# OECU_BASE3.net
KiCad netlist of a schematic drawn in Altium Designer
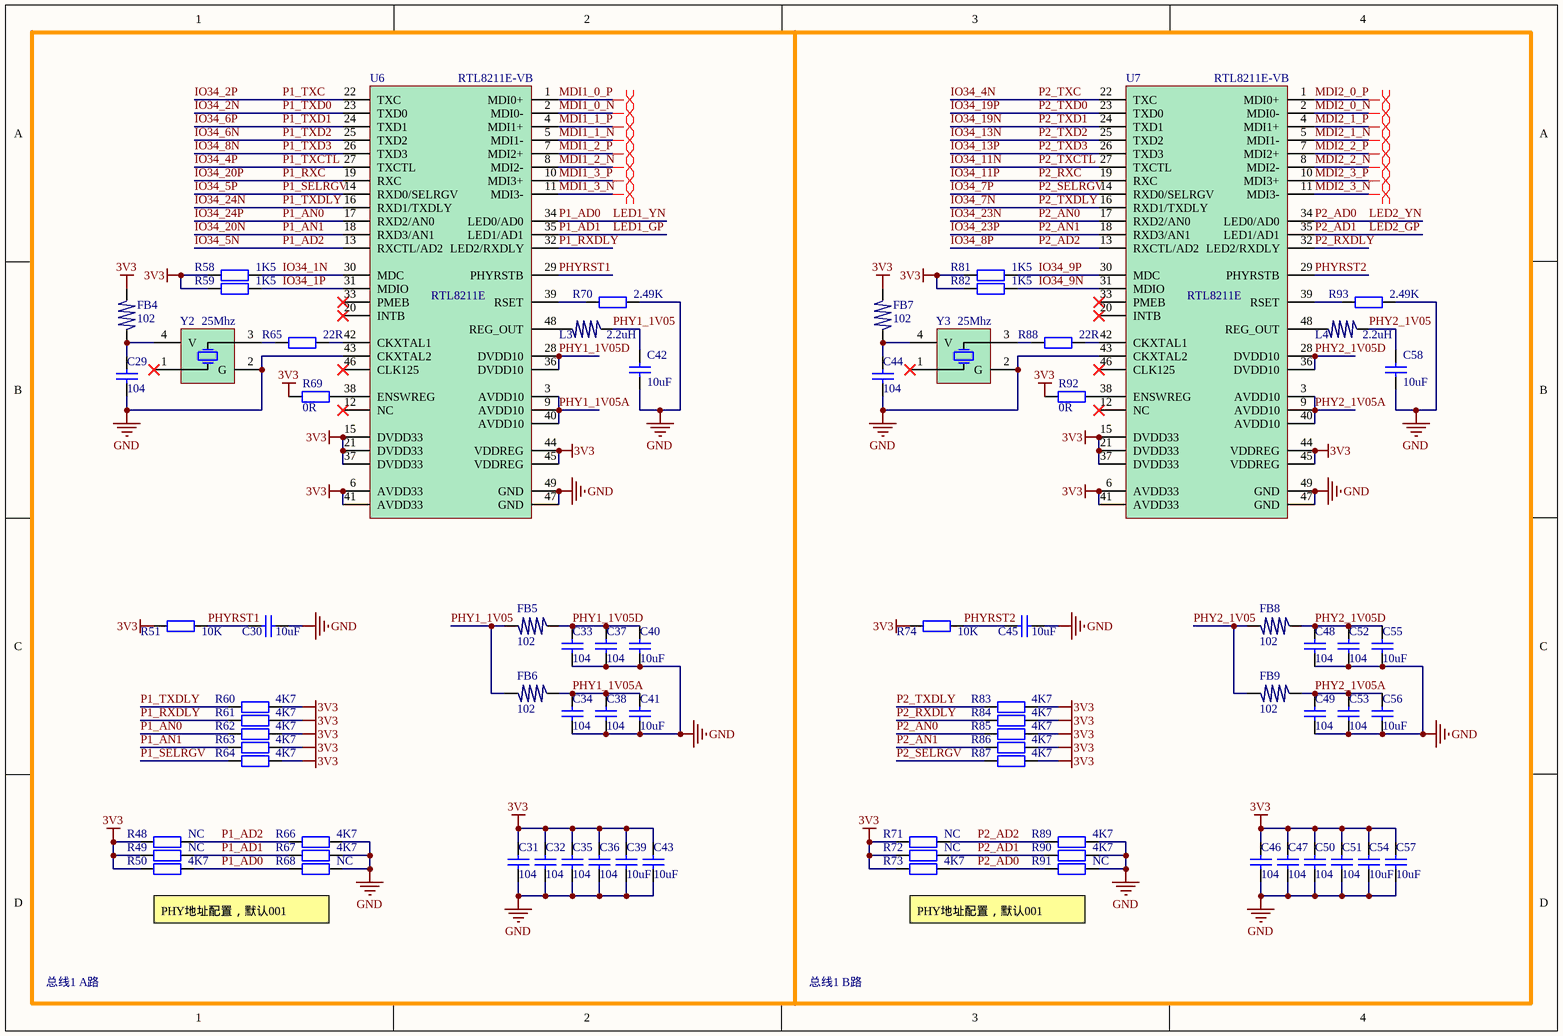
[diagram p0: OECU_BASE3.SchDoc]

(export (version "E")
  (design (tool "Eeschema 10.0.6"))
  (components
    (comp (ref "C29")
      (value "104")
      (footprint "0402")
      (description "贴片电容 0402")
      (libsource (lib "MT_Device") (part "CAP_0402"))
    )
    (comp (ref "C30")
      (value "10uF")
      (footprint "0402")
      (description "贴片电容 0402")
      (libsource (lib "MT_Device") (part "CAP_0402"))
    )
    (comp (ref "C31")
      (value "104")
      (footprint "0402")
      (description "贴片电容 0402")
      (libsource (lib "MT_Device") (part "CAP_0402"))
    )
    (comp (ref "C32")
      (value "104")
      (footprint "0402")
      (description "贴片电容 0402")
      (libsource (lib "MT_Device") (part "CAP_0402"))
    )
    (comp (ref "C33")
      (value "104")
      (footprint "0402")
      (description "贴片电容 0402")
      (libsource (lib "MT_Device") (part "CAP_0402"))
    )
    (comp (ref "C34")
      (value "104")
      (footprint "0402")
      (description "贴片电容 0402")
      (libsource (lib "MT_Device") (part "CAP_0402"))
    )
    (comp (ref "C35")
      (value "104")
      (footprint "0402")
      (description "贴片电容 0402")
      (libsource (lib "MT_Device") (part "CAP_0402"))
    )
    (comp (ref "C36")
      (value "104")
      (footprint "0402")
      (description "贴片电容 0402")
      (libsource (lib "MT_Device") (part "CAP_0402"))
    )
    (comp (ref "C37")
      (value "104")
      (footprint "0402")
      (description "贴片电容 0402")
      (libsource (lib "MT_Device") (part "CAP_0402"))
    )
    (comp (ref "C38")
      (value "104")
      (footprint "0402")
      (description "贴片电容 0402")
      (libsource (lib "MT_Device") (part "CAP_0402"))
    )
    (comp (ref "C39")
      (value "10uF")
      (footprint "0402")
      (description "贴片电容 0402")
      (libsource (lib "MT_Device") (part "CAP_0402"))
    )
    (comp (ref "C40")
      (value "10uF")
      (footprint "0402")
      (description "贴片电容 0402")
      (libsource (lib "MT_Device") (part "CAP_0402"))
    )
    (comp (ref "C41")
      (value "10uF")
      (footprint "0402")
      (description "贴片电容 0402")
      (libsource (lib "MT_Device") (part "CAP_0402"))
    )
    (comp (ref "C42")
      (value "10uF")
      (footprint "0402")
      (description "贴片电容 0402")
      (libsource (lib "MT_Device") (part "CAP_0402"))
    )
    (comp (ref "C43")
      (value "10uF")
      (footprint "0402")
      (description "贴片电容 0402")
      (libsource (lib "MT_Device") (part "CAP_0402"))
    )
    (comp (ref "C44")
      (value "104")
      (footprint "0402")
      (description "贴片电容 0402")
      (libsource (lib "MT_Device") (part "CAP_0402"))
    )
    (comp (ref "C45")
      (value "10uF")
      (footprint "0402")
      (description "贴片电容 0402")
      (libsource (lib "MT_Device") (part "CAP_0402"))
    )
    (comp (ref "C46")
      (value "104")
      (footprint "0402")
      (description "贴片电容 0402")
      (libsource (lib "MT_Device") (part "CAP_0402"))
    )
    (comp (ref "C47")
      (value "104")
      (footprint "0402")
      (description "贴片电容 0402")
      (libsource (lib "MT_Device") (part "CAP_0402"))
    )
    (comp (ref "C48")
      (value "104")
      (footprint "0402")
      (description "贴片电容 0402")
      (libsource (lib "MT_Device") (part "CAP_0402"))
    )
    (comp (ref "C49")
      (value "104")
      (footprint "0402")
      (description "贴片电容 0402")
      (libsource (lib "MT_Device") (part "CAP_0402"))
    )
    (comp (ref "C50")
      (value "104")
      (footprint "0402")
      (description "贴片电容 0402")
      (libsource (lib "MT_Device") (part "CAP_0402"))
    )
    (comp (ref "C51")
      (value "104")
      (footprint "0402")
      (description "贴片电容 0402")
      (libsource (lib "MT_Device") (part "CAP_0402"))
    )
    (comp (ref "C52")
      (value "104")
      (footprint "0402")
      (description "贴片电容 0402")
      (libsource (lib "MT_Device") (part "CAP_0402"))
    )
    (comp (ref "C53")
      (value "104")
      (footprint "0402")
      (description "贴片电容 0402")
      (libsource (lib "MT_Device") (part "CAP_0402"))
    )
    (comp (ref "C54")
      (value "10uF")
      (footprint "0402")
      (description "贴片电容 0402")
      (libsource (lib "MT_Device") (part "CAP_0402"))
    )
    (comp (ref "C55")
      (value "10uF")
      (footprint "0402")
      (description "贴片电容 0402")
      (libsource (lib "MT_Device") (part "CAP_0402"))
    )
    (comp (ref "C56")
      (value "10uF")
      (footprint "0402")
      (description "贴片电容 0402")
      (libsource (lib "MT_Device") (part "CAP_0402"))
    )
    (comp (ref "C57")
      (value "10uF")
      (footprint "0402")
      (description "贴片电容 0402")
      (libsource (lib "MT_Device") (part "CAP_0402"))
    )
    (comp (ref "C58")
      (value "10uF")
      (footprint "0402")
      (description "贴片电容 0402")
      (libsource (lib "MT_Device") (part "CAP_0402"))
    )
    (comp (ref "FB4")
      (value "102")
      (footprint "0402")
      (description "磁珠 0402")
      (libsource (lib "MT_Device") (part "FB_0402"))
    )
    (comp (ref "FB5")
      (value "102")
      (footprint "0603")
      (description "磁珠 0603")
      (libsource (lib "MT_Device") (part "FB_0603"))
    )
    (comp (ref "FB6")
      (value "102")
      (footprint "0603")
      (description "磁珠 0603")
      (libsource (lib "MT_Device") (part "FB_0603"))
    )
    (comp (ref "FB7")
      (value "102")
      (footprint "0402")
      (description "磁珠 0402")
      (libsource (lib "MT_Device") (part "FB_0402"))
    )
    (comp (ref "FB8")
      (value "102")
      (footprint "0603")
      (description "磁珠 0603")
      (libsource (lib "MT_Device") (part "FB_0603"))
    )
    (comp (ref "FB9")
      (value "102")
      (footprint "0603")
      (description "磁珠 0603")
      (libsource (lib "MT_Device") (part "FB_0603"))
    )
    (comp (ref "L3")
      (value "2.2uH")
      (footprint "0805")
      (description "电感 0805")
      (libsource (lib "MT_Device") (part "L_0805"))
    )
    (comp (ref "L4")
      (value "2.2uH")
      (footprint "0805")
      (description "电感 0805")
      (libsource (lib "MT_Device") (part "L_0805"))
    )
    (comp (ref "R48")
      (value "NC")
      (footprint "R_0402")
      (description "电阻 0402")
      (libsource (lib "MT_Device") (part "RES_0402"))
    )
    (comp (ref "R49")
      (value "NC")
      (footprint "R_0402")
      (description "电阻 0402")
      (libsource (lib "MT_Device") (part "RES_0402"))
    )
    (comp (ref "R50")
      (value "4K7")
      (footprint "R_0402")
      (description "电阻 0402")
      (libsource (lib "MT_Device") (part "RES_0402"))
    )
    (comp (ref "R51")
      (value "10K")
      (footprint "R_0402")
      (description "电阻 0402")
      (libsource (lib "MT_Device") (part "RES_0402"))
    )
    (comp (ref "R58")
      (value "1K5")
      (footprint "R_0402")
      (description "电阻 0402")
      (libsource (lib "") (part "RES_0402_1"))
    )
    (comp (ref "R59")
      (value "1K5")
      (footprint "R_0402")
      (description "电阻 0402")
      (libsource (lib "") (part "RES_0402_1"))
    )
    (comp (ref "R60")
      (value "4K7")
      (footprint "R_0402")
      (description "电阻 0402")
      (libsource (lib "MT_Device") (part "RES_0402"))
    )
    (comp (ref "R61")
      (value "4K7")
      (footprint "R_0402")
      (description "电阻 0402")
      (libsource (lib "MT_Device") (part "RES_0402"))
    )
    (comp (ref "R62")
      (value "4K7")
      (footprint "R_0402")
      (description "电阻 0402")
      (libsource (lib "MT_Device") (part "RES_0402"))
    )
    (comp (ref "R63")
      (value "4K7")
      (footprint "R_0402")
      (description "电阻 0402")
      (libsource (lib "MT_Device") (part "RES_0402"))
    )
    (comp (ref "R64")
      (value "4K7")
      (footprint "R_0402")
      (description "电阻 0402")
      (libsource (lib "MT_Device") (part "RES_0402"))
    )
    (comp (ref "R65")
      (value "22R")
      (footprint "R_0402")
      (description "电阻 0402")
      (libsource (lib "") (part "RES_0402_1"))
    )
    (comp (ref "R66")
      (value "4K7")
      (footprint "R_0402")
      (description "电阻 0402")
      (libsource (lib "MT_Device") (part "RES_0402"))
    )
    (comp (ref "R67")
      (value "4K7")
      (footprint "R_0402")
      (description "电阻 0402")
      (libsource (lib "MT_Device") (part "RES_0402"))
    )
    (comp (ref "R68")
      (value "NC")
      (footprint "R_0402")
      (description "电阻 0402")
      (libsource (lib "MT_Device") (part "RES_0402"))
    )
    (comp (ref "R69")
      (value "0R")
      (footprint "R_0402")
      (description "电阻 0402")
      (libsource (lib "") (part "RES_0402_1"))
    )
    (comp (ref "R70")
      (value "2.49K")
      (footprint "R_0402")
      (description "电阻 0402")
      (libsource (lib "MT_Device") (part "RES_0402"))
    )
    (comp (ref "R71")
      (value "NC")
      (footprint "R_0402")
      (description "电阻 0402")
      (libsource (lib "MT_Device") (part "RES_0402"))
    )
    (comp (ref "R72")
      (value "NC")
      (footprint "R_0402")
      (description "电阻 0402")
      (libsource (lib "MT_Device") (part "RES_0402"))
    )
    (comp (ref "R73")
      (value "4K7")
      (footprint "R_0402")
      (description "电阻 0402")
      (libsource (lib "MT_Device") (part "RES_0402"))
    )
    (comp (ref "R74")
      (value "10K")
      (footprint "R_0402")
      (description "电阻 0402")
      (libsource (lib "MT_Device") (part "RES_0402"))
    )
    (comp (ref "R81")
      (value "1K5")
      (footprint "R_0402")
      (description "电阻 0402")
      (libsource (lib "") (part "RES_0402_1"))
    )
    (comp (ref "R82")
      (value "1K5")
      (footprint "R_0402")
      (description "电阻 0402")
      (libsource (lib "") (part "RES_0402_1"))
    )
    (comp (ref "R83")
      (value "4K7")
      (footprint "R_0402")
      (description "电阻 0402")
      (libsource (lib "MT_Device") (part "RES_0402"))
    )
    (comp (ref "R84")
      (value "4K7")
      (footprint "R_0402")
      (description "电阻 0402")
      (libsource (lib "MT_Device") (part "RES_0402"))
    )
    (comp (ref "R85")
      (value "4K7")
      (footprint "R_0402")
      (description "电阻 0402")
      (libsource (lib "MT_Device") (part "RES_0402"))
    )
    (comp (ref "R86")
      (value "4K7")
      (footprint "R_0402")
      (description "电阻 0402")
      (libsource (lib "MT_Device") (part "RES_0402"))
    )
    (comp (ref "R87")
      (value "4K7")
      (footprint "R_0402")
      (description "电阻 0402")
      (libsource (lib "MT_Device") (part "RES_0402"))
    )
    (comp (ref "R88")
      (value "22R")
      (footprint "R_0402")
      (description "电阻 0402")
      (libsource (lib "") (part "RES_0402_1"))
    )
    (comp (ref "R89")
      (value "4K7")
      (footprint "R_0402")
      (description "电阻 0402")
      (libsource (lib "MT_Device") (part "RES_0402"))
    )
    (comp (ref "R90")
      (value "4K7")
      (footprint "R_0402")
      (description "电阻 0402")
      (libsource (lib "MT_Device") (part "RES_0402"))
    )
    (comp (ref "R91")
      (value "NC")
      (footprint "R_0402")
      (description "电阻 0402")
      (libsource (lib "MT_Device") (part "RES_0402"))
    )
    (comp (ref "R92")
      (value "0R")
      (footprint "R_0402")
      (description "电阻 0402")
      (libsource (lib "") (part "RES_0402_1"))
    )
    (comp (ref "R93")
      (value "2.49K")
      (footprint "R_0402")
      (description "电阻 0402")
      (libsource (lib "MT_Device") (part "RES_0402"))
    )
    (comp (ref "U6")
      (value "RTL8211E-VB")
      (footprint "QFN48")
      (description "QFN48")
      (libsource (lib "MT_Chip") (part "RTL8211E"))
    )
    (comp (ref "U7")
      (value "RTL8211E-VB")
      (footprint "QFN48")
      (description "QFN48")
      (libsource (lib "MT_Chip") (part "RTL8211E"))
    )
    (comp (ref "Y2") (value "25Mhz") (footprint "XTAL_3225") (libsource (lib "MT_Device") (part "XTAL_3225")))
    (comp (ref "Y3") (value "25Mhz") (footprint "XTAL_3225") (libsource (lib "MT_Device") (part "XTAL_3225")))
  )
  (nets
    (net (code "1") (name "/IO34_1N") (class "Default")
      (node (ref "R58") (pin "1") (pinfunction "1_1") (pintype "passive"))
      (node (ref "U6") (pin "30") (pinfunction "MDC_30") (pintype "passive"))
    )
    (net (code "2") (name "/IO34_1P") (class "Default")
      (node (ref "R59") (pin "1") (pinfunction "1_1") (pintype "passive"))
      (node (ref "U6") (pin "31") (pinfunction "MDIO_31") (pintype "passive"))
    )
    (net (code "3") (name "/IO34_2N") (class "Default")
      (node (ref "U6") (pin "23") (pinfunction "TXD0_23") (pintype "passive"))
    )
    (net (code "4") (name "/IO34_2P") (class "Default")
      (node (ref "U6") (pin "22") (pinfunction "TXC_22") (pintype "passive"))
    )
    (net (code "5") (name "/IO34_4N") (class "Default")
      (node (ref "U7") (pin "22") (pinfunction "TXC_22") (pintype "passive"))
    )
    (net (code "6") (name "/IO34_4P") (class "Default")
      (node (ref "U6") (pin "27") (pinfunction "TXCTL_27") (pintype "passive"))
    )
    (net (code "7") (name "/IO34_5N") (class "Default")
      (node (ref "R48") (pin "2") (pinfunction "2_2") (pintype "passive"))
      (node (ref "R66") (pin "1") (pinfunction "1_1") (pintype "passive"))
      (node (ref "U6") (pin "13") (pinfunction "RXCTL/AD2_13") (pintype "passive"))
    )
    (net (code "8") (name "/IO34_5P") (class "Default")
      (node (ref "R64") (pin "1") (pinfunction "1_1") (pintype "passive"))
      (node (ref "U6") (pin "14") (pinfunction "RXD0/SELRGV_14") (pintype "passive"))
    )
    (net (code "9") (name "/IO34_6N") (class "Default")
      (node (ref "U6") (pin "25") (pinfunction "TXD2_25") (pintype "passive"))
    )
    (net (code "10") (name "/IO34_6P") (class "Default")
      (node (ref "U6") (pin "24") (pinfunction "TXD1_24") (pintype "passive"))
    )
    (net (code "11") (name "/IO34_7N") (class "Default")
      (node (ref "R83") (pin "1") (pinfunction "1_1") (pintype "passive"))
      (node (ref "U7") (pin "16") (pinfunction "RXD1/TXDLY_16") (pintype "passive"))
    )
    (net (code "12") (name "/IO34_7P") (class "Default")
      (node (ref "R87") (pin "1") (pinfunction "1_1") (pintype "passive"))
      (node (ref "U7") (pin "14") (pinfunction "RXD0/SELRGV_14") (pintype "passive"))
    )
    (net (code "13") (name "/IO34_8N") (class "Default")
      (node (ref "U6") (pin "26") (pinfunction "TXD3_26") (pintype "passive"))
    )
    (net (code "14") (name "/IO34_8P") (class "Default")
      (node (ref "R71") (pin "2") (pinfunction "2_2") (pintype "passive"))
      (node (ref "R89") (pin "1") (pinfunction "1_1") (pintype "passive"))
      (node (ref "U7") (pin "13") (pinfunction "RXCTL/AD2_13") (pintype "passive"))
    )
    (net (code "15") (name "/IO34_9N") (class "Default")
      (node (ref "R82") (pin "1") (pinfunction "1_1") (pintype "passive"))
      (node (ref "U7") (pin "31") (pinfunction "MDIO_31") (pintype "passive"))
    )
    (net (code "16") (name "/IO34_9P") (class "Default")
      (node (ref "R81") (pin "1") (pinfunction "1_1") (pintype "passive"))
      (node (ref "U7") (pin "30") (pinfunction "MDC_30") (pintype "passive"))
    )
    (net (code "17") (name "/IO34_11N") (class "Default")
      (node (ref "U7") (pin "27") (pinfunction "TXCTL_27") (pintype "passive"))
    )
    (net (code "18") (name "/IO34_11P") (class "Default")
      (node (ref "U7") (pin "19") (pinfunction "RXC_19") (pintype "passive"))
    )
    (net (code "19") (name "/IO34_13N") (class "Default")
      (node (ref "U7") (pin "25") (pinfunction "TXD2_25") (pintype "passive"))
    )
    (net (code "20") (name "/IO34_13P") (class "Default")
      (node (ref "U7") (pin "26") (pinfunction "TXD3_26") (pintype "passive"))
    )
    (net (code "21") (name "/IO34_19N") (class "Default")
      (node (ref "U7") (pin "24") (pinfunction "TXD1_24") (pintype "passive"))
    )
    (net (code "22") (name "/IO34_19P") (class "Default")
      (node (ref "U7") (pin "23") (pinfunction "TXD0_23") (pintype "passive"))
    )
    (net (code "23") (name "/IO34_20N") (class "Default")
      (node (ref "R63") (pin "1") (pinfunction "1_1") (pintype "passive"))
      (node (ref "U6") (pin "18") (pinfunction "RXD3/AN1_18") (pintype "passive"))
    )
    (net (code "24") (name "/IO34_20P") (class "Default")
      (node (ref "U6") (pin "19") (pinfunction "RXC_19") (pintype "passive"))
    )
    (net (code "25") (name "/IO34_23N") (class "Default")
      (node (ref "R85") (pin "1") (pinfunction "1_1") (pintype "passive"))
      (node (ref "U7") (pin "17") (pinfunction "RXD2/AN0_17") (pintype "passive"))
    )
    (net (code "26") (name "/IO34_23P") (class "Default")
      (node (ref "R86") (pin "1") (pinfunction "1_1") (pintype "passive"))
      (node (ref "U7") (pin "18") (pinfunction "RXD3/AN1_18") (pintype "passive"))
    )
    (net (code "27") (name "/IO34_24N") (class "Default")
      (node (ref "R60") (pin "1") (pinfunction "1_1") (pintype "passive"))
      (node (ref "U6") (pin "16") (pinfunction "RXD1/TXDLY_16") (pintype "passive"))
    )
    (net (code "28") (name "/IO34_24P") (class "Default")
      (node (ref "R62") (pin "1") (pinfunction "1_1") (pintype "passive"))
      (node (ref "U6") (pin "17") (pinfunction "RXD2/AN0_17") (pintype "passive"))
    )
    (net (code "29") (name "/LED1_GP") (class "Default")
      (node (ref "R49") (pin "2") (pinfunction "2_2") (pintype "passive"))
      (node (ref "R67") (pin "1") (pinfunction "1_1") (pintype "passive"))
      (node (ref "U6") (pin "35") (pinfunction "LED1/AD1_35") (pintype "passive"))
    )
    (net (code "30") (name "/LED1_YN") (class "Default")
      (node (ref "R50") (pin "2") (pinfunction "2_2") (pintype "passive"))
      (node (ref "R68") (pin "1") (pinfunction "1_1") (pintype "passive"))
      (node (ref "U6") (pin "34") (pinfunction "LED0/AD0_34") (pintype "passive"))
    )
    (net (code "31") (name "/LED2_GP") (class "Default")
      (node (ref "R72") (pin "2") (pinfunction "2_2") (pintype "passive"))
      (node (ref "R90") (pin "1") (pinfunction "1_1") (pintype "passive"))
      (node (ref "U7") (pin "35") (pinfunction "LED1/AD1_35") (pintype "passive"))
    )
    (net (code "32") (name "/LED2_YN") (class "Default")
      (node (ref "R73") (pin "2") (pinfunction "2_2") (pintype "passive"))
      (node (ref "R91") (pin "1") (pinfunction "1_1") (pintype "passive"))
      (node (ref "U7") (pin "34") (pinfunction "LED0/AD0_34") (pintype "passive"))
    )
    (net (code "33") (name "/MDI1_0_N") (class "Default")
      (node (ref "U6") (pin "2") (pinfunction "MDI0-_2") (pintype "passive"))
    )
    (net (code "34") (name "/MDI1_0_P") (class "Default")
      (node (ref "U6") (pin "1") (pinfunction "MDI0+_1") (pintype "passive"))
    )
    (net (code "35") (name "/MDI1_1_N") (class "Default")
      (node (ref "U6") (pin "5") (pinfunction "MDI1-_5") (pintype "passive"))
    )
    (net (code "36") (name "/MDI1_1_P") (class "Default")
      (node (ref "U6") (pin "4") (pinfunction "MDI1+_4") (pintype "passive"))
    )
    (net (code "37") (name "/MDI1_2_N") (class "Default")
      (node (ref "U6") (pin "8") (pinfunction "MDI2-_8") (pintype "passive"))
    )
    (net (code "38") (name "/MDI1_2_P") (class "Default")
      (node (ref "U6") (pin "7") (pinfunction "MDI2+_7") (pintype "passive"))
    )
    (net (code "39") (name "/MDI1_3_N") (class "Default")
      (node (ref "U6") (pin "11") (pinfunction "MDI3-_11") (pintype "passive"))
    )
    (net (code "40") (name "/MDI1_3_P") (class "Default")
      (node (ref "U6") (pin "10") (pinfunction "MDI3+_10") (pintype "passive"))
    )
    (net (code "41") (name "/MDI2_0_N") (class "Default")
      (node (ref "U7") (pin "2") (pinfunction "MDI0-_2") (pintype "passive"))
    )
    (net (code "42") (name "/MDI2_0_P") (class "Default")
      (node (ref "U7") (pin "1") (pinfunction "MDI0+_1") (pintype "passive"))
    )
    (net (code "43") (name "/MDI2_1_N") (class "Default")
      (node (ref "U7") (pin "5") (pinfunction "MDI1-_5") (pintype "passive"))
    )
    (net (code "44") (name "/MDI2_1_P") (class "Default")
      (node (ref "U7") (pin "4") (pinfunction "MDI1+_4") (pintype "passive"))
    )
    (net (code "45") (name "/MDI2_2_N") (class "Default")
      (node (ref "U7") (pin "8") (pinfunction "MDI2-_8") (pintype "passive"))
    )
    (net (code "46") (name "/MDI2_2_P") (class "Default")
      (node (ref "U7") (pin "7") (pinfunction "MDI2+_7") (pintype "passive"))
    )
    (net (code "47") (name "/MDI2_3_N") (class "Default")
      (node (ref "U7") (pin "11") (pinfunction "MDI3-_11") (pintype "passive"))
    )
    (net (code "48") (name "/MDI2_3_P") (class "Default")
      (node (ref "U7") (pin "10") (pinfunction "MDI3+_10") (pintype "passive"))
    )
    (net (code "49") (name "/P1_RXDLY") (class "Default")
      (node (ref "R61") (pin "1") (pinfunction "1_1") (pintype "passive"))
      (node (ref "U6") (pin "32") (pinfunction "LED2/RXDLY_32") (pintype "passive"))
    )
    (net (code "50") (name "/P2_RXDLY") (class "Default")
      (node (ref "R84") (pin "1") (pinfunction "1_1") (pintype "passive"))
      (node (ref "U7") (pin "32") (pinfunction "LED2/RXDLY_32") (pintype "passive"))
    )
    (net (code "51") (name "/PHY1_1V05") (class "Default")
      (node (ref "C42") (pin "2") (pinfunction "2_2") (pintype "passive"))
      (node (ref "FB5") (pin "1") (pintype "passive"))
      (node (ref "FB6") (pin "1") (pintype "passive"))
      (node (ref "L3") (pin "1") (pintype "passive"))
    )
    (net (code "52") (name "/PHY1_1V05A") (class "Default")
      (node (ref "C34") (pin "2") (pinfunction "2_2") (pintype "passive"))
      (node (ref "C38") (pin "2") (pinfunction "2_2") (pintype "passive"))
      (node (ref "C41") (pin "2") (pinfunction "2_2") (pintype "passive"))
      (node (ref "FB6") (pin "2") (pintype "passive"))
      (node (ref "U6") (pin "3") (pinfunction "AVDD10_3") (pintype "passive"))
      (node (ref "U6") (pin "40") (pinfunction "AVDD10_40") (pintype "passive"))
      (node (ref "U6") (pin "9") (pinfunction "AVDD10_9") (pintype "passive"))
    )
    (net (code "53") (name "/PHY1_1V05D") (class "Default")
      (node (ref "C33") (pin "2") (pinfunction "2_2") (pintype "passive"))
      (node (ref "C37") (pin "2") (pinfunction "2_2") (pintype "passive"))
      (node (ref "C40") (pin "2") (pinfunction "2_2") (pintype "passive"))
      (node (ref "FB5") (pin "2") (pintype "passive"))
      (node (ref "U6") (pin "28") (pinfunction "DVDD10_28") (pintype "passive"))
      (node (ref "U6") (pin "36") (pinfunction "DVDD10_36") (pintype "passive"))
    )
    (net (code "54") (name "/PHY2_1V05") (class "Default")
      (node (ref "C58") (pin "2") (pinfunction "2_2") (pintype "passive"))
      (node (ref "FB8") (pin "1") (pintype "passive"))
      (node (ref "FB9") (pin "1") (pintype "passive"))
      (node (ref "L4") (pin "1") (pintype "passive"))
    )
    (net (code "55") (name "/PHY2_1V05A") (class "Default")
      (node (ref "C49") (pin "2") (pinfunction "2_2") (pintype "passive"))
      (node (ref "C53") (pin "2") (pinfunction "2_2") (pintype "passive"))
      (node (ref "C56") (pin "2") (pinfunction "2_2") (pintype "passive"))
      (node (ref "FB9") (pin "2") (pintype "passive"))
      (node (ref "U7") (pin "3") (pinfunction "AVDD10_3") (pintype "passive"))
      (node (ref "U7") (pin "40") (pinfunction "AVDD10_40") (pintype "passive"))
      (node (ref "U7") (pin "9") (pinfunction "AVDD10_9") (pintype "passive"))
    )
    (net (code "56") (name "/PHY2_1V05D") (class "Default")
      (node (ref "C48") (pin "2") (pinfunction "2_2") (pintype "passive"))
      (node (ref "C52") (pin "2") (pinfunction "2_2") (pintype "passive"))
      (node (ref "C55") (pin "2") (pinfunction "2_2") (pintype "passive"))
      (node (ref "FB8") (pin "2") (pintype "passive"))
      (node (ref "U7") (pin "28") (pinfunction "DVDD10_28") (pintype "passive"))
      (node (ref "U7") (pin "36") (pinfunction "DVDD10_36") (pintype "passive"))
    )
    (net (code "57") (name "/PHYRST1") (class "Default")
      (node (ref "C30") (pin "1") (pinfunction "1_1") (pintype "passive"))
      (node (ref "R51") (pin "2") (pinfunction "2_2") (pintype "passive"))
      (node (ref "U6") (pin "29") (pinfunction "PHYRSTB_29") (pintype "passive"))
    )
    (net (code "58") (name "/PHYRST2") (class "Default")
      (node (ref "C45") (pin "1") (pinfunction "1_1") (pintype "passive"))
      (node (ref "R74") (pin "2") (pinfunction "2_2") (pintype "passive"))
      (node (ref "U7") (pin "29") (pinfunction "PHYRSTB_29") (pintype "passive"))
    )
    (net (code "59") (name "3V3") (class "Default")
      (node (ref "C31") (pin "1") (pinfunction "1_1") (pintype "passive"))
      (node (ref "C32") (pin "1") (pinfunction "1_1") (pintype "passive"))
      (node (ref "C35") (pin "1") (pinfunction "1_1") (pintype "passive"))
      (node (ref "C36") (pin "1") (pinfunction "1_1") (pintype "passive"))
      (node (ref "C39") (pin "1") (pinfunction "1_1") (pintype "passive"))
      (node (ref "C43") (pin "1") (pinfunction "1_1") (pintype "passive"))
      (node (ref "C46") (pin "1") (pinfunction "1_1") (pintype "passive"))
      (node (ref "C47") (pin "1") (pinfunction "1_1") (pintype "passive"))
      (node (ref "C50") (pin "1") (pinfunction "1_1") (pintype "passive"))
      (node (ref "C51") (pin "1") (pinfunction "1_1") (pintype "passive"))
      (node (ref "C54") (pin "1") (pinfunction "1_1") (pintype "passive"))
      (node (ref "C57") (pin "1") (pinfunction "1_1") (pintype "passive"))
      (node (ref "FB4") (pin "2") (pintype "passive"))
      (node (ref "FB7") (pin "2") (pintype "passive"))
      (node (ref "R48") (pin "1") (pinfunction "1_1") (pintype "passive"))
      (node (ref "R49") (pin "1") (pinfunction "1_1") (pintype "passive"))
      (node (ref "R50") (pin "1") (pinfunction "1_1") (pintype "passive"))
      (node (ref "R51") (pin "1") (pinfunction "1_1") (pintype "passive"))
      (node (ref "R58") (pin "2") (pinfunction "2_2") (pintype "passive"))
      (node (ref "R59") (pin "2") (pinfunction "2_2") (pintype "passive"))
      (node (ref "R60") (pin "2") (pinfunction "2_2") (pintype "passive"))
      (node (ref "R61") (pin "2") (pinfunction "2_2") (pintype "passive"))
      (node (ref "R62") (pin "2") (pinfunction "2_2") (pintype "passive"))
      (node (ref "R63") (pin "2") (pinfunction "2_2") (pintype "passive"))
      (node (ref "R64") (pin "2") (pinfunction "2_2") (pintype "passive"))
      (node (ref "R69") (pin "2") (pinfunction "2_2") (pintype "passive"))
      (node (ref "R71") (pin "1") (pinfunction "1_1") (pintype "passive"))
      (node (ref "R72") (pin "1") (pinfunction "1_1") (pintype "passive"))
      (node (ref "R73") (pin "1") (pinfunction "1_1") (pintype "passive"))
      (node (ref "R74") (pin "1") (pinfunction "1_1") (pintype "passive"))
      (node (ref "R81") (pin "2") (pinfunction "2_2") (pintype "passive"))
      (node (ref "R82") (pin "2") (pinfunction "2_2") (pintype "passive"))
      (node (ref "R83") (pin "2") (pinfunction "2_2") (pintype "passive"))
      (node (ref "R84") (pin "2") (pinfunction "2_2") (pintype "passive"))
      (node (ref "R85") (pin "2") (pinfunction "2_2") (pintype "passive"))
      (node (ref "R86") (pin "2") (pinfunction "2_2") (pintype "passive"))
      (node (ref "R87") (pin "2") (pinfunction "2_2") (pintype "passive"))
      (node (ref "R92") (pin "2") (pinfunction "2_2") (pintype "passive"))
      (node (ref "U6") (pin "15") (pinfunction "DVDD33_15") (pintype "passive"))
      (node (ref "U6") (pin "21") (pinfunction "DVDD33_21") (pintype "passive"))
      (node (ref "U6") (pin "37") (pinfunction "DVDD33_37") (pintype "passive"))
      (node (ref "U6") (pin "41") (pinfunction "AVDD33_41") (pintype "passive"))
      (node (ref "U6") (pin "44") (pinfunction "VDDREG_44") (pintype "passive"))
      (node (ref "U6") (pin "45") (pinfunction "VDDREG_45") (pintype "passive"))
      (node (ref "U6") (pin "6") (pinfunction "AVDD33_6") (pintype "passive"))
      (node (ref "U7") (pin "15") (pinfunction "DVDD33_15") (pintype "passive"))
      (node (ref "U7") (pin "21") (pinfunction "DVDD33_21") (pintype "passive"))
      (node (ref "U7") (pin "37") (pinfunction "DVDD33_37") (pintype "passive"))
      (node (ref "U7") (pin "41") (pinfunction "AVDD33_41") (pintype "passive"))
      (node (ref "U7") (pin "44") (pinfunction "VDDREG_44") (pintype "passive"))
      (node (ref "U7") (pin "45") (pinfunction "VDDREG_45") (pintype "passive"))
      (node (ref "U7") (pin "6") (pinfunction "AVDD33_6") (pintype "passive"))
    )
    (net (code "60") (name "GND") (class "Default")
      (node (ref "C29") (pin "1") (pinfunction "1_1") (pintype "passive"))
      (node (ref "C30") (pin "2") (pinfunction "2_2") (pintype "passive"))
      (node (ref "C31") (pin "2") (pinfunction "2_2") (pintype "passive"))
      (node (ref "C32") (pin "2") (pinfunction "2_2") (pintype "passive"))
      (node (ref "C33") (pin "1") (pinfunction "1_1") (pintype "passive"))
      (node (ref "C34") (pin "1") (pinfunction "1_1") (pintype "passive"))
      (node (ref "C35") (pin "2") (pinfunction "2_2") (pintype "passive"))
      (node (ref "C36") (pin "2") (pinfunction "2_2") (pintype "passive"))
      (node (ref "C37") (pin "1") (pinfunction "1_1") (pintype "passive"))
      (node (ref "C38") (pin "1") (pinfunction "1_1") (pintype "passive"))
      (node (ref "C39") (pin "2") (pinfunction "2_2") (pintype "passive"))
      (node (ref "C40") (pin "1") (pinfunction "1_1") (pintype "passive"))
      (node (ref "C41") (pin "1") (pinfunction "1_1") (pintype "passive"))
      (node (ref "C42") (pin "1") (pinfunction "1_1") (pintype "passive"))
      (node (ref "C43") (pin "2") (pinfunction "2_2") (pintype "passive"))
      (node (ref "C44") (pin "1") (pinfunction "1_1") (pintype "passive"))
      (node (ref "C45") (pin "2") (pinfunction "2_2") (pintype "passive"))
      (node (ref "C46") (pin "2") (pinfunction "2_2") (pintype "passive"))
      (node (ref "C47") (pin "2") (pinfunction "2_2") (pintype "passive"))
      (node (ref "C48") (pin "1") (pinfunction "1_1") (pintype "passive"))
      (node (ref "C49") (pin "1") (pinfunction "1_1") (pintype "passive"))
      (node (ref "C50") (pin "2") (pinfunction "2_2") (pintype "passive"))
      (node (ref "C51") (pin "2") (pinfunction "2_2") (pintype "passive"))
      (node (ref "C52") (pin "1") (pinfunction "1_1") (pintype "passive"))
      (node (ref "C53") (pin "1") (pinfunction "1_1") (pintype "passive"))
      (node (ref "C54") (pin "2") (pinfunction "2_2") (pintype "passive"))
      (node (ref "C55") (pin "1") (pinfunction "1_1") (pintype "passive"))
      (node (ref "C56") (pin "1") (pinfunction "1_1") (pintype "passive"))
      (node (ref "C57") (pin "2") (pinfunction "2_2") (pintype "passive"))
      (node (ref "C58") (pin "1") (pinfunction "1_1") (pintype "passive"))
      (node (ref "R66") (pin "2") (pinfunction "2_2") (pintype "passive"))
      (node (ref "R67") (pin "2") (pinfunction "2_2") (pintype "passive"))
      (node (ref "R68") (pin "2") (pinfunction "2_2") (pintype "passive"))
      (node (ref "R70") (pin "2") (pinfunction "2_2") (pintype "passive"))
      (node (ref "R89") (pin "2") (pinfunction "2_2") (pintype "passive"))
      (node (ref "R90") (pin "2") (pinfunction "2_2") (pintype "passive"))
      (node (ref "R91") (pin "2") (pinfunction "2_2") (pintype "passive"))
      (node (ref "R93") (pin "2") (pinfunction "2_2") (pintype "passive"))
      (node (ref "U6") (pin "43") (pinfunction "CKXTAL2_43") (pintype "passive"))
      (node (ref "U6") (pin "47") (pinfunction "GND_47") (pintype "passive"))
      (node (ref "U6") (pin "49") (pinfunction "GND_49") (pintype "passive"))
      (node (ref "U7") (pin "43") (pinfunction "CKXTAL2_43") (pintype "passive"))
      (node (ref "U7") (pin "47") (pinfunction "GND_47") (pintype "passive"))
      (node (ref "U7") (pin "49") (pinfunction "GND_49") (pintype "passive"))
      (node (ref "Y2") (pin "2") (pinfunction "G_2") (pintype "passive"))
      (node (ref "Y3") (pin "2") (pinfunction "G_2") (pintype "passive"))
    )
    (net (code "61") (name "Net-(U6-CKXTAL1)") (class "Default")
      (node (ref "R65") (pin "1") (pinfunction "1_1") (pintype "passive"))
      (node (ref "U6") (pin "42") (pinfunction "CKXTAL1_42") (pintype "passive"))
    )
    (net (code "62") (name "Net-(U6-ENSWREG)") (class "Default")
      (node (ref "R69") (pin "1") (pinfunction "1_1") (pintype "passive"))
      (node (ref "U6") (pin "38") (pinfunction "ENSWREG_38") (pintype "passive"))
    )
    (net (code "63") (name "Net-(U6-REG_OUT)") (class "Default")
      (node (ref "L3") (pin "2") (pintype "passive"))
      (node (ref "U6") (pin "48") (pinfunction "REG_OUT_48") (pintype "passive"))
    )
    (net (code "64") (name "Net-(U6-RSET)") (class "Default")
      (node (ref "R70") (pin "1") (pinfunction "1_1") (pintype "passive"))
      (node (ref "U6") (pin "39") (pinfunction "RSET_39") (pintype "passive"))
    )
    (net (code "65") (name "Net-(U7-CKXTAL1)") (class "Default")
      (node (ref "R88") (pin "1") (pinfunction "1_1") (pintype "passive"))
      (node (ref "U7") (pin "42") (pinfunction "CKXTAL1_42") (pintype "passive"))
    )
    (net (code "66") (name "Net-(U7-ENSWREG)") (class "Default")
      (node (ref "R92") (pin "1") (pinfunction "1_1") (pintype "passive"))
      (node (ref "U7") (pin "38") (pinfunction "ENSWREG_38") (pintype "passive"))
    )
    (net (code "67") (name "Net-(U7-REG_OUT)") (class "Default")
      (node (ref "L4") (pin "2") (pintype "passive"))
      (node (ref "U7") (pin "48") (pinfunction "REG_OUT_48") (pintype "passive"))
    )
    (net (code "68") (name "Net-(U7-RSET)") (class "Default")
      (node (ref "R93") (pin "1") (pinfunction "1_1") (pintype "passive"))
      (node (ref "U7") (pin "39") (pinfunction "RSET_39") (pintype "passive"))
    )
    (net (code "69") (name "Net-(Y2-OP)") (class "Default")
      (node (ref "R65") (pin "2") (pinfunction "2_2") (pintype "passive"))
      (node (ref "Y2") (pin "3") (pinfunction "OP_3") (pintype "passive"))
    )
    (net (code "70") (name "Net-(Y2-V)") (class "Default")
      (node (ref "C29") (pin "2") (pinfunction "2_2") (pintype "passive"))
      (node (ref "FB4") (pin "1") (pintype "passive"))
      (node (ref "Y2") (pin "4") (pinfunction "V_4") (pintype "passive"))
    )
    (net (code "71") (name "Net-(Y3-OP)") (class "Default")
      (node (ref "R88") (pin "2") (pinfunction "2_2") (pintype "passive"))
      (node (ref "Y3") (pin "3") (pinfunction "OP_3") (pintype "passive"))
    )
    (net (code "72") (name "Net-(Y3-V)") (class "Default")
      (node (ref "C44") (pin "2") (pinfunction "2_2") (pintype "passive"))
      (node (ref "FB7") (pin "1") (pintype "passive"))
      (node (ref "Y3") (pin "4") (pinfunction "V_4") (pintype "passive"))
    )
    (net (code "73") (name "unconnected-(U6-CLK125-Pad46)") (class "Default")
      (node (ref "U6") (pin "46") (pinfunction "CLK125_46") (pintype "passive+no_connect"))
    )
    (net (code "74") (name "unconnected-(U6-INTB-Pad20)") (class "Default")
      (node (ref "U6") (pin "20") (pinfunction "INTB_20") (pintype "passive+no_connect"))
    )
    (net (code "75") (name "unconnected-(U6-NC-Pad12)") (class "Default")
      (node (ref "U6") (pin "12") (pinfunction "NC_12") (pintype "passive+no_connect"))
    )
    (net (code "76") (name "unconnected-(U6-PMEB-Pad33)") (class "Default")
      (node (ref "U6") (pin "33") (pinfunction "PMEB_33") (pintype "passive+no_connect"))
    )
    (net (code "77") (name "unconnected-(U7-CLK125-Pad46)") (class "Default")
      (node (ref "U7") (pin "46") (pinfunction "CLK125_46") (pintype "passive+no_connect"))
    )
    (net (code "78") (name "unconnected-(U7-INTB-Pad20)") (class "Default")
      (node (ref "U7") (pin "20") (pinfunction "INTB_20") (pintype "passive+no_connect"))
    )
    (net (code "79") (name "unconnected-(U7-NC-Pad12)") (class "Default")
      (node (ref "U7") (pin "12") (pinfunction "NC_12") (pintype "passive+no_connect"))
    )
    (net (code "80") (name "unconnected-(U7-PMEB-Pad33)") (class "Default")
      (node (ref "U7") (pin "33") (pinfunction "PMEB_33") (pintype "passive+no_connect"))
    )
    (net (code "81") (name "unconnected-(Y2-EC-Pad1)") (class "Default")
      (node (ref "Y2") (pin "1") (pinfunction "EC_1") (pintype "passive+no_connect"))
    )
    (net (code "82") (name "unconnected-(Y3-EC-Pad1)") (class "Default")
      (node (ref "Y3") (pin "1") (pinfunction "EC_1") (pintype "passive+no_connect"))
    )
  )
)
